# Connectors.net
KiCad netlist of a schematic drawn in Altium Designer
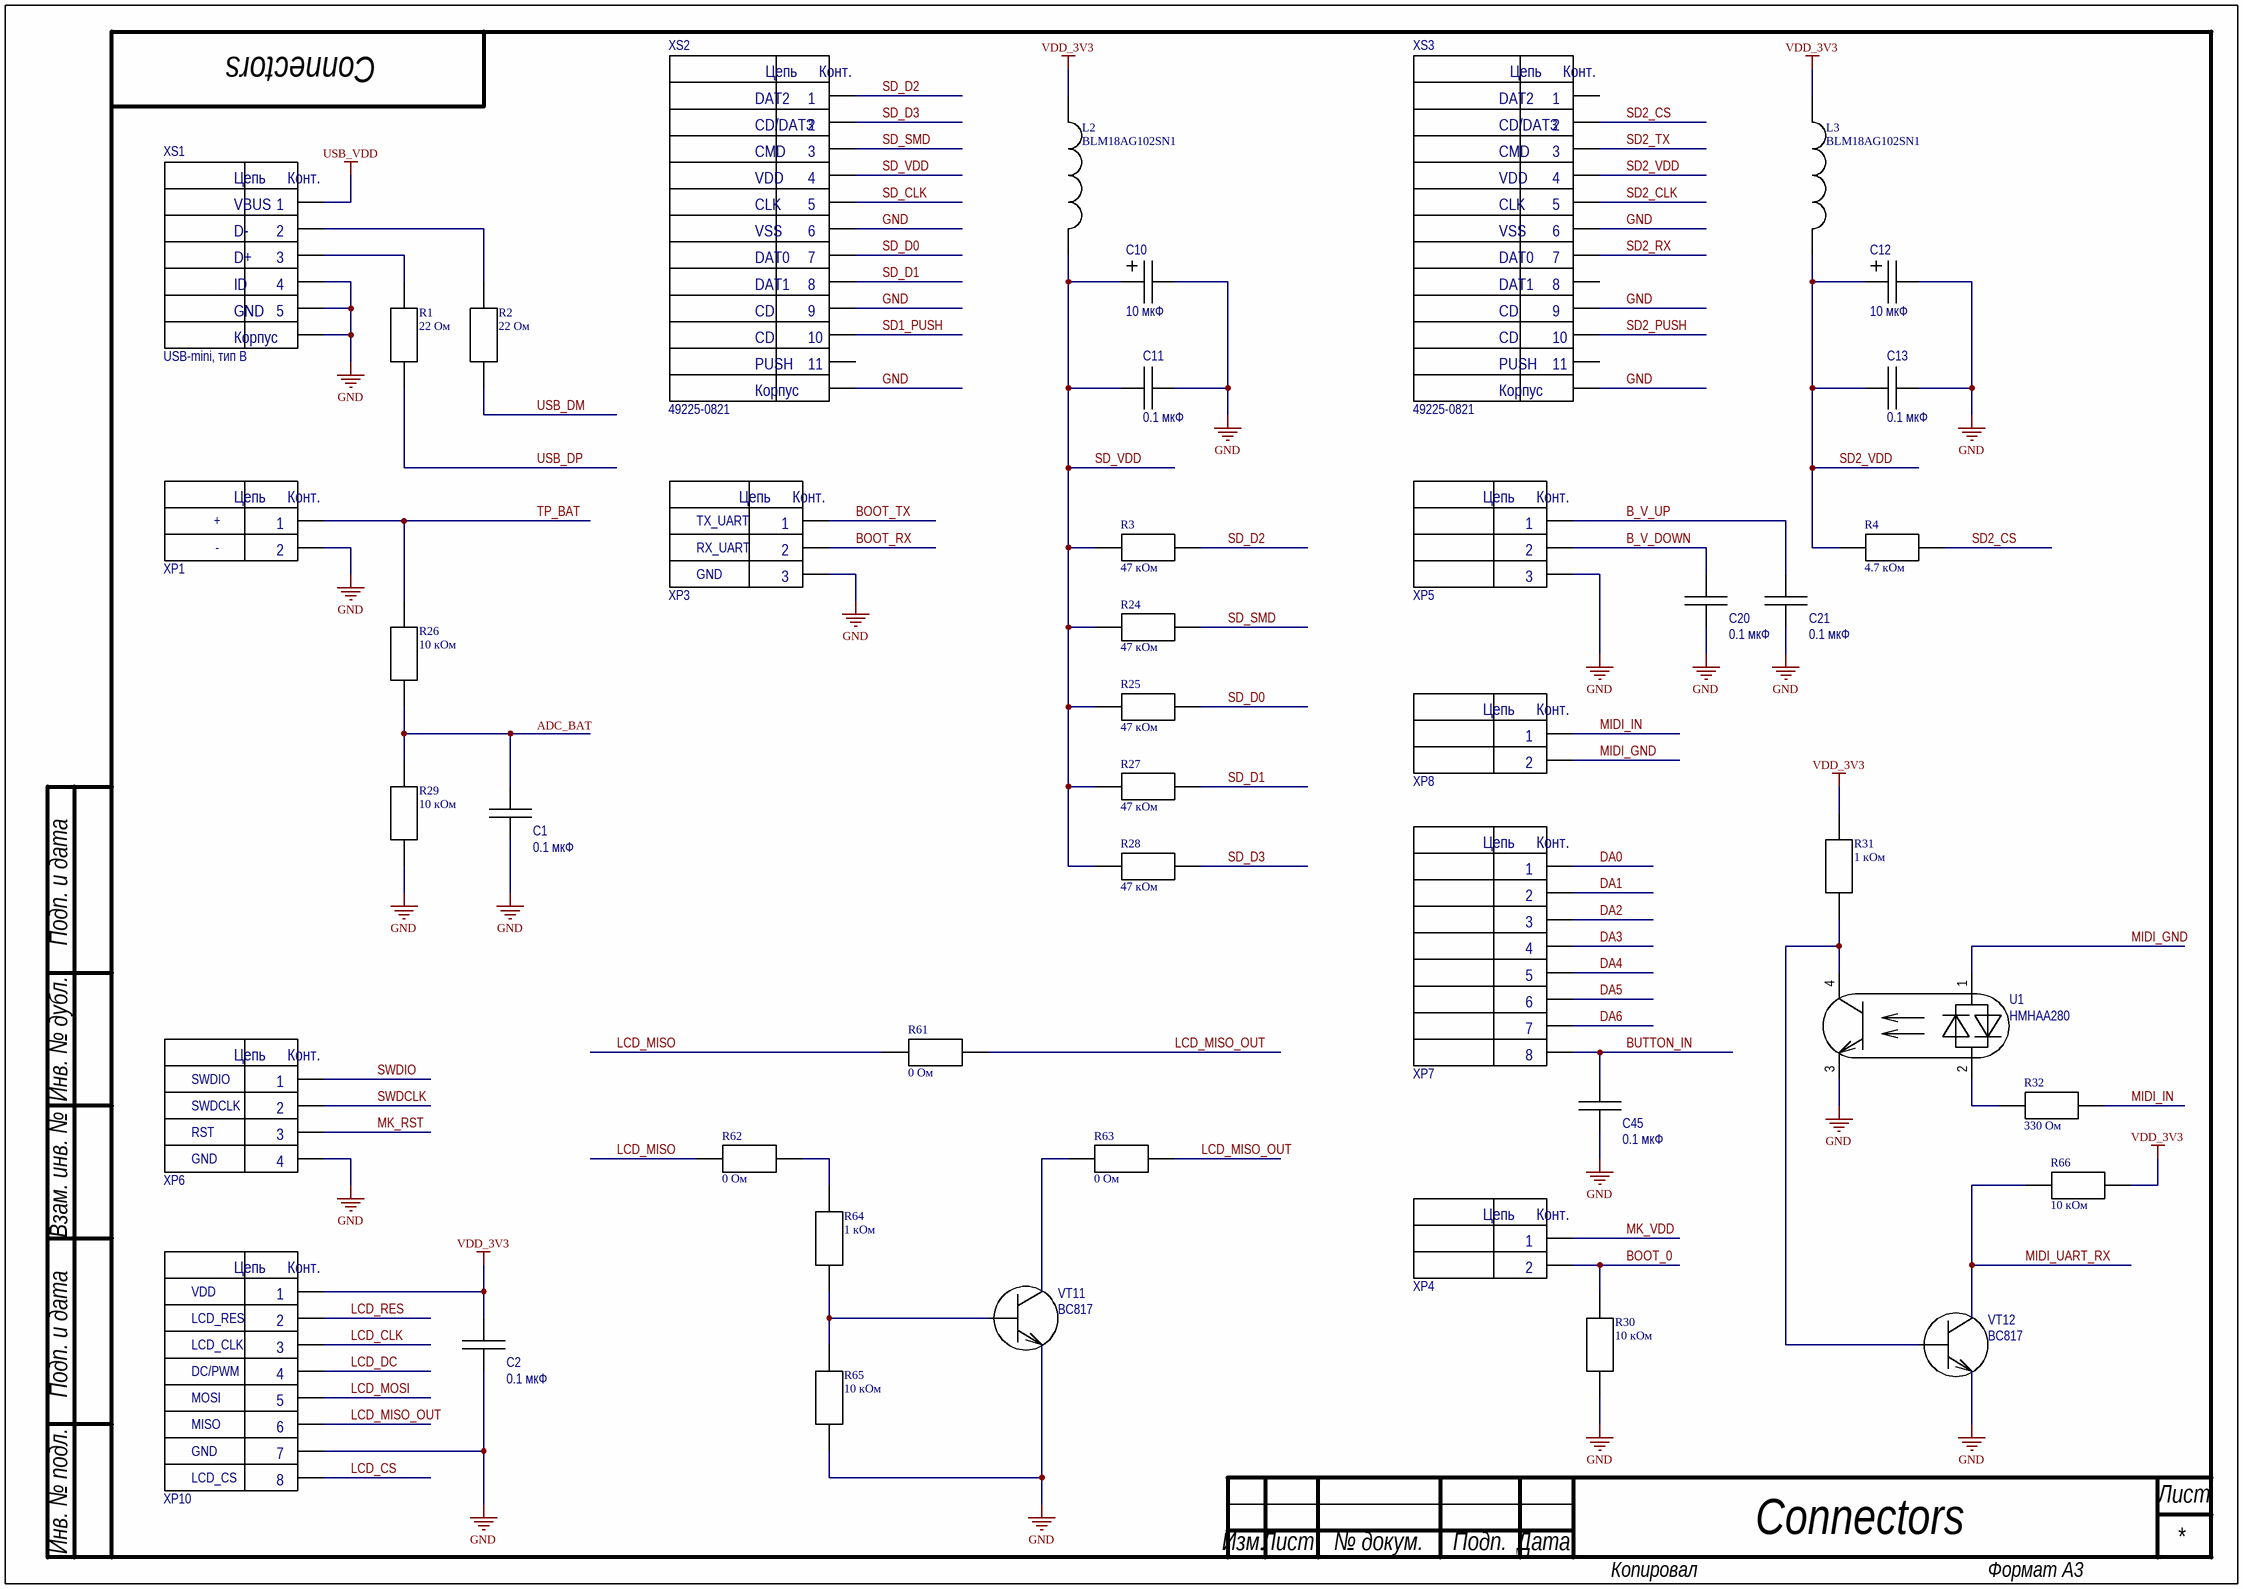
[diagram p0: Connectors.SchDoc]

(export (version "E")
  (design (tool "Eeschema 10.0.6"))
  (components
    (comp (ref "C1")
      (value "0.1 мкФ")
      (footprint "C 1206")
      (description "SMD Capacitor 1206")
      (fields
        (field (name "TOLERANCE") "/Укажите допуск в процентах/")
        (field (name "MANUFACTURER") "/Укажите компанию-производителя/")
      )
      (libsource (lib "my_lib") (part "CAP 1206"))
    )
    (comp (ref "C2")
      (value "0.1 мкФ")
      (footprint "C 1206")
      (description "SMD Capacitor 1206")
      (fields
        (field (name "TOLERANCE") "/Укажите допуск в процентах/")
        (field (name "MANUFACTURER") "/Укажите компанию-производителя/")
      )
      (libsource (lib "my_lib") (part "CAP 1206"))
    )
    (comp (ref "C10")
      (value "10 мкФ")
      (footprint "C TAN_C")
      (description "SMD Tantalium Capacitor C")
      (fields
        (field (name "TOLERANCE") "/Укажите допуск в процентах/")
        (field (name "MANUFACTURER") "/Укажите компанию-производителя/")
      )
      (libsource (lib "my_lib") (part "CAP TAN_C"))
    )
    (comp (ref "C11")
      (value "0.1 мкФ")
      (footprint "C 1206")
      (description "SMD Capacitor 1206")
      (fields
        (field (name "TOLERANCE") "/Укажите допуск в процентах/")
        (field (name "MANUFACTURER") "/Укажите компанию-производителя/")
      )
      (libsource (lib "my_lib") (part "CAP 1206"))
    )
    (comp (ref "C12")
      (value "10 мкФ")
      (footprint "C TAN_C")
      (description "SMD Tantalium Capacitor C")
      (fields
        (field (name "TOLERANCE") "/Укажите допуск в процентах/")
        (field (name "MANUFACTURER") "/Укажите компанию-производителя/")
      )
      (libsource (lib "my_lib") (part "CAP TAN_C"))
    )
    (comp (ref "C13")
      (value "0.1 мкФ")
      (footprint "C 1206")
      (description "SMD Capacitor 1206")
      (fields
        (field (name "TOLERANCE") "/Укажите допуск в процентах/")
        (field (name "MANUFACTURER") "/Укажите компанию-производителя/")
      )
      (libsource (lib "my_lib") (part "CAP 1206"))
    )
    (comp (ref "C20")
      (value "0.1 мкФ")
      (footprint "C 1206")
      (description "SMD Capacitor 1206")
      (fields
        (field (name "TOLERANCE") "/Укажите допуск в процентах/")
        (field (name "MANUFACTURER") "/Укажите компанию-производителя/")
      )
      (libsource (lib "my_lib") (part "CAP 1206"))
    )
    (comp (ref "C21")
      (value "0.1 мкФ")
      (footprint "C 1206")
      (description "SMD Capacitor 1206")
      (fields
        (field (name "TOLERANCE") "/Укажите допуск в процентах/")
        (field (name "MANUFACTURER") "/Укажите компанию-производителя/")
      )
      (libsource (lib "my_lib") (part "CAP 1206"))
    )
    (comp (ref "C45")
      (value "0.1 мкФ")
      (footprint "C 1206")
      (description "SMD Capacitor 1206")
      (fields
        (field (name "TOLERANCE") "/Укажите допуск в процентах/")
        (field (name "MANUFACTURER") "/Укажите компанию-производителя/")
      )
      (libsource (lib "my_lib") (part "CAP 1206"))
    )
    (comp (ref "L2")
      (value "BLM18AG102SN1")
      (footprint "FB 0603")
      (libsource (lib "my_lib") (part "BLM18AG102SN1"))
    )
    (comp (ref "L3")
      (value "BLM18AG102SN1")
      (footprint "FB 0603")
      (libsource (lib "my_lib") (part "BLM18AG102SN1"))
    )
    (comp (ref "R1") (value "22 Ом") (footprint "RES 0805") (libsource (lib "my_lib") (part "RES 0805")))
    (comp (ref "R2") (value "22 Ом") (footprint "RES 0805") (libsource (lib "my_lib") (part "RES 0805")))
    (comp (ref "R3") (value "47 кОм") (footprint "RES 0805") (libsource (lib "my_lib") (part "RES 0805")))
    (comp (ref "R4") (value "4.7 кОм") (footprint "RES 0805") (libsource (lib "my_lib") (part "RES 0805")))
    (comp (ref "R24") (value "47 кОм") (footprint "RES 0805") (libsource (lib "my_lib") (part "RES 0805")))
    (comp (ref "R25") (value "47 кОм") (footprint "RES 0805") (libsource (lib "my_lib") (part "RES 0805")))
    (comp (ref "R26") (value "10 кОм") (footprint "RES 0805") (libsource (lib "my_lib") (part "RES 0805")))
    (comp (ref "R27") (value "47 кОм") (footprint "RES 0805") (libsource (lib "my_lib") (part "RES 0805")))
    (comp (ref "R28") (value "47 кОм") (footprint "RES 0805") (libsource (lib "my_lib") (part "RES 0805")))
    (comp (ref "R29") (value "10 кОм") (footprint "RES 0805") (libsource (lib "my_lib") (part "RES 0805")))
    (comp (ref "R30") (value "10 кОм") (footprint "RES 0805") (libsource (lib "my_lib") (part "RES 0805")))
    (comp (ref "R31") (value "1 кОм") (footprint "RES 0805") (libsource (lib "my_lib") (part "RES 0805")))
    (comp (ref "R32") (value "330 Ом") (footprint "RES 0805") (libsource (lib "my_lib") (part "RES 0805")))
    (comp (ref "R61") (value "0 Ом") (footprint "RES 0805") (libsource (lib "my_lib") (part "RES 0805")))
    (comp (ref "R62") (value "0 Ом") (footprint "RES 0805") (libsource (lib "my_lib") (part "RES 0805")))
    (comp (ref "R63") (value "0 Ом") (footprint "RES 0805") (libsource (lib "my_lib") (part "RES 0805")))
    (comp (ref "R64") (value "1 кОм") (footprint "RES 0805") (libsource (lib "my_lib") (part "RES 0805")))
    (comp (ref "R65") (value "10 кОм") (footprint "RES 0805") (libsource (lib "my_lib") (part "RES 0805")))
    (comp (ref "R66") (value "10 кОм") (footprint "RES 0805") (libsource (lib "my_lib") (part "RES 0805")))
    (comp (ref "U1")
      (value "HMHAA280")
      (footprint "MFP-4L")
      (description "AC Input Half Pitch Mini-Flat Package 4-pin Optocoupler")
      (fields (field (name "MANUFACTURER") "Fairchild Semiconductor"))
      (libsource (lib "my_lib") (part "HMHAA280"))
    )
    (comp (ref "VT11")
      (value "BC817")
      (footprint "SOT-23")
      (description "NPN general-purpose transistor")
      (fields (field (name "MANUFACTURER") "NXP"))
      (libsource (lib "my_lib") (part "BC817"))
    )
    (comp (ref "VT12")
      (value "BC817")
      (footprint "SOT-23")
      (description "NPN general-purpose transistor")
      (fields (field (name "MANUFACTURER") "NXP"))
      (libsource (lib "my_lib") (part "BC817"))
    )
    (comp (ref "XP1")
      (value "PLS-2")
      (footprint "PLS-2")
      (description "PLS connector")
      (fields (field (name "MANUFACTURER") "NONAME"))
      (libsource (lib "my_lib") (part "PLS-2"))
    )
    (comp (ref "XP3")
      (value "PLS-3")
      (footprint "PLS-3")
      (description "PLS connector")
      (fields (field (name "MANUFACTURER") "NONAME"))
      (libsource (lib "my_lib") (part "PLS-3"))
    )
    (comp (ref "XP4")
      (value "PLS-2")
      (footprint "PLS-2")
      (description "PLS connector")
      (fields (field (name "MANUFACTURER") "NONAME"))
      (libsource (lib "my_lib") (part "PLS-2"))
    )
    (comp (ref "XP5")
      (value "PLS-3")
      (footprint "PLS-3")
      (description "PLS connector")
      (fields (field (name "MANUFACTURER") "NONAME"))
      (libsource (lib "my_lib") (part "PLS-3"))
    )
    (comp (ref "XP6")
      (value "PLD-4")
      (footprint "PLD-4")
      (description "PLD connector")
      (fields (field (name "MANUFACTURER") "NONAME"))
      (libsource (lib "my_lib") (part "PLD-4"))
    )
    (comp (ref "XP7")
      (value "PLD-8")
      (footprint "PLD-8")
      (description "PLD connector")
      (fields (field (name "MANUFACTURER") "NONAME"))
      (libsource (lib "my_lib") (part "PLD-8"))
    )
    (comp (ref "XP8")
      (value "PLS-2")
      (footprint "PLS-2")
      (description "PLS connector")
      (fields (field (name "MANUFACTURER") "NONAME"))
      (libsource (lib "my_lib") (part "PLS-2"))
    )
    (comp (ref "XP10")
      (value "PLD-8")
      (footprint "PLD-8")
      (description "PLD connector")
      (fields (field (name "MANUFACTURER") "NONAME"))
      (libsource (lib "my_lib") (part "PLD-8"))
    )
    (comp (ref "XS1")
      (value "USB-mini, тип B")
      (footprint "USB_mini_B")
      (description "USB-mini-B connector")
      (fields (field (name "MANUFACTURER") "NONAME"))
      (libsource (lib "my_lib") (part "USB-mini_B"))
    )
    (comp (ref "XS2")
      (value "49225-0821")
      (footprint "MOLEX 49225-0821")
      (description "MOLEX MicroSD connector")
      (fields (field (name "MANUFACTURER") "Molex"))
      (libsource (lib "my_lib") (part "49225-0821"))
    )
    (comp (ref "XS3")
      (value "49225-0821")
      (footprint "MOLEX 49225-0821")
      (description "MOLEX MicroSD connector")
      (fields (field (name "MANUFACTURER") "Molex"))
      (libsource (lib "my_lib") (part "49225-0821"))
    )
  )
  (nets
    (net (code "1") (name "/ADC_BAT") (class "Default")
      (node (ref "C1") (pin "1") (pinfunction "1_1") (pintype "passive"))
      (node (ref "R26") (pin "1") (pinfunction "1_1") (pintype "passive"))
      (node (ref "R29") (pin "2") (pinfunction "2_2") (pintype "passive"))
    )
    (net (code "2") (name "/BOOT_0") (class "Default")
      (node (ref "R30") (pin "2") (pinfunction "2_2") (pintype "passive"))
      (node (ref "XP4") (pin "2") (pinfunction "2_2") (pintype "passive"))
    )
    (net (code "3") (name "/BOOT_RX") (class "Default")
      (node (ref "XP3") (pin "2") (pinfunction "2_2") (pintype "passive"))
    )
    (net (code "4") (name "/BOOT_TX") (class "Default")
      (node (ref "XP3") (pin "1") (pinfunction "1_1") (pintype "passive"))
    )
    (net (code "5") (name "/BUTTON_IN") (class "Default")
      (node (ref "C45") (pin "1") (pinfunction "1_1") (pintype "passive"))
      (node (ref "XP7") (pin "8") (pinfunction "8_8") (pintype "passive"))
    )
    (net (code "6") (name "/B_V_DOWN") (class "Default")
      (node (ref "C20") (pin "1") (pinfunction "1_1") (pintype "passive"))
      (node (ref "XP5") (pin "2") (pinfunction "2_2") (pintype "passive"))
    )
    (net (code "7") (name "/B_V_UP") (class "Default")
      (node (ref "C21") (pin "1") (pinfunction "1_1") (pintype "passive"))
      (node (ref "XP5") (pin "1") (pinfunction "1_1") (pintype "passive"))
    )
    (net (code "8") (name "/DA0") (class "Default")
      (node (ref "XP7") (pin "1") (pinfunction "1_1") (pintype "passive"))
    )
    (net (code "9") (name "/DA1") (class "Default")
      (node (ref "XP7") (pin "2") (pinfunction "2_2") (pintype "passive"))
    )
    (net (code "10") (name "/DA2") (class "Default")
      (node (ref "XP7") (pin "3") (pinfunction "3_3") (pintype "passive"))
    )
    (net (code "11") (name "/DA3") (class "Default")
      (node (ref "XP7") (pin "4") (pinfunction "4_4") (pintype "passive"))
    )
    (net (code "12") (name "/DA4") (class "Default")
      (node (ref "XP7") (pin "5") (pinfunction "5_5") (pintype "passive"))
    )
    (net (code "13") (name "/DA5") (class "Default")
      (node (ref "XP7") (pin "6") (pinfunction "6_6") (pintype "passive"))
    )
    (net (code "14") (name "/DA6") (class "Default")
      (node (ref "XP7") (pin "7") (pinfunction "7_7") (pintype "passive"))
    )
    (net (code "15") (name "/LCD_CLK") (class "Default")
      (node (ref "XP10") (pin "3") (pinfunction "3_3") (pintype "passive"))
    )
    (net (code "16") (name "/LCD_CS") (class "Default")
      (node (ref "XP10") (pin "8") (pinfunction "8_8") (pintype "passive"))
    )
    (net (code "17") (name "/LCD_DC") (class "Default")
      (node (ref "XP10") (pin "4") (pinfunction "4_4") (pintype "passive"))
    )
    (net (code "18") (name "/LCD_MISO") (class "Default")
      (node (ref "R61") (pin "1") (pinfunction "1_1") (pintype "passive"))
      (node (ref "R62") (pin "2") (pinfunction "2_2") (pintype "passive"))
    )
    (net (code "19") (name "/LCD_MISO_OUT") (class "Default")
      (node (ref "R61") (pin "2") (pinfunction "2_2") (pintype "passive"))
      (node (ref "R63") (pin "1") (pinfunction "1_1") (pintype "passive"))
      (node (ref "XP10") (pin "6") (pinfunction "6_6") (pintype "passive"))
    )
    (net (code "20") (name "/LCD_MOSI") (class "Default")
      (node (ref "XP10") (pin "5") (pinfunction "5_5") (pintype "passive"))
    )
    (net (code "21") (name "/LCD_RES") (class "Default")
      (node (ref "XP10") (pin "2") (pinfunction "2_2") (pintype "passive"))
    )
    (net (code "22") (name "/MIDI_GND") (class "Default")
      (node (ref "U1") (pin "1") (pinfunction "AC_1") (pintype "passive"))
      (node (ref "XP8") (pin "2") (pinfunction "2_2") (pintype "passive"))
    )
    (net (code "23") (name "/MIDI_IN") (class "Default")
      (node (ref "R32") (pin "2") (pinfunction "2_2") (pintype "passive"))
      (node (ref "XP8") (pin "1") (pinfunction "1_1") (pintype "passive"))
    )
    (net (code "24") (name "/MIDI_UART_RX") (class "Default")
      (node (ref "R66") (pin "1") (pinfunction "1_1") (pintype "passive"))
      (node (ref "VT12") (pin "3") (pinfunction "C_3") (pintype "passive"))
    )
    (net (code "25") (name "/MK_RST") (class "Default")
      (node (ref "XP6") (pin "3") (pinfunction "3_3") (pintype "passive"))
    )
    (net (code "26") (name "/MK_VDD") (class "Default")
      (node (ref "XP4") (pin "1") (pinfunction "1_1") (pintype "passive"))
    )
    (net (code "27") (name "/SD1_PUSH") (class "Default")
      (node (ref "XS2") (pin "10") (pinfunction "10_10") (pintype "passive"))
    )
    (net (code "28") (name "/SD2_CLK") (class "Default")
      (node (ref "XS3") (pin "5") (pinfunction "5_5") (pintype "passive"))
    )
    (net (code "29") (name "/SD2_CS") (class "Default")
      (node (ref "R4") (pin "2") (pinfunction "2_2") (pintype "passive"))
      (node (ref "XS3") (pin "2") (pinfunction "2_2") (pintype "passive"))
    )
    (net (code "30") (name "/SD2_PUSH") (class "Default")
      (node (ref "XS3") (pin "10") (pinfunction "10_10") (pintype "passive"))
    )
    (net (code "31") (name "/SD2_RX") (class "Default")
      (node (ref "XS3") (pin "7") (pinfunction "7_7") (pintype "passive"))
    )
    (net (code "32") (name "/SD2_TX") (class "Default")
      (node (ref "XS3") (pin "3") (pinfunction "3_3") (pintype "passive"))
    )
    (net (code "33") (name "/SD2_VDD") (class "Default")
      (node (ref "C12") (pin "1") (pinfunction "1_1") (pintype "passive"))
      (node (ref "C13") (pin "1") (pinfunction "1_1") (pintype "passive"))
      (node (ref "L3") (pin "2") (pinfunction "2_2") (pintype "passive"))
      (node (ref "R4") (pin "1") (pinfunction "1_1") (pintype "passive"))
      (node (ref "XS3") (pin "4") (pinfunction "4_4") (pintype "passive"))
    )
    (net (code "34") (name "/SD_CLK") (class "Default")
      (node (ref "XS2") (pin "5") (pinfunction "5_5") (pintype "passive"))
    )
    (net (code "35") (name "/SD_D0") (class "Default")
      (node (ref "R25") (pin "2") (pinfunction "2_2") (pintype "passive"))
      (node (ref "XS2") (pin "7") (pinfunction "7_7") (pintype "passive"))
    )
    (net (code "36") (name "/SD_D1") (class "Default")
      (node (ref "R27") (pin "2") (pinfunction "2_2") (pintype "passive"))
      (node (ref "XS2") (pin "8") (pinfunction "8_8") (pintype "passive"))
    )
    (net (code "37") (name "/SD_D2") (class "Default")
      (node (ref "R3") (pin "2") (pinfunction "2_2") (pintype "passive"))
      (node (ref "XS2") (pin "1") (pinfunction "1_1") (pintype "passive"))
    )
    (net (code "38") (name "/SD_D3") (class "Default")
      (node (ref "R28") (pin "2") (pinfunction "2_2") (pintype "passive"))
      (node (ref "XS2") (pin "2") (pinfunction "2_2") (pintype "passive"))
    )
    (net (code "39") (name "/SD_SMD") (class "Default")
      (node (ref "R24") (pin "2") (pinfunction "2_2") (pintype "passive"))
      (node (ref "XS2") (pin "3") (pinfunction "3_3") (pintype "passive"))
    )
    (net (code "40") (name "/SD_VDD") (class "Default")
      (node (ref "C10") (pin "1") (pinfunction "1_1") (pintype "passive"))
      (node (ref "C11") (pin "1") (pinfunction "1_1") (pintype "passive"))
      (node (ref "L2") (pin "2") (pinfunction "2_2") (pintype "passive"))
      (node (ref "R24") (pin "1") (pinfunction "1_1") (pintype "passive"))
      (node (ref "R25") (pin "1") (pinfunction "1_1") (pintype "passive"))
      (node (ref "R27") (pin "1") (pinfunction "1_1") (pintype "passive"))
      (node (ref "R28") (pin "1") (pinfunction "1_1") (pintype "passive"))
      (node (ref "R3") (pin "1") (pinfunction "1_1") (pintype "passive"))
      (node (ref "XS2") (pin "4") (pinfunction "4_4") (pintype "passive"))
    )
    (net (code "41") (name "/SWDCLK") (class "Default")
      (node (ref "XP6") (pin "2") (pinfunction "2_2") (pintype "passive"))
    )
    (net (code "42") (name "/SWDIO") (class "Default")
      (node (ref "XP6") (pin "1") (pinfunction "1_1") (pintype "passive"))
    )
    (net (code "43") (name "/TP_BAT") (class "Default")
      (node (ref "R26") (pin "2") (pinfunction "2_2") (pintype "passive"))
      (node (ref "XP1") (pin "1") (pinfunction "1_1") (pintype "passive"))
    )
    (net (code "44") (name "/USB_DM") (class "Default")
      (node (ref "R2") (pin "1") (pinfunction "1_1") (pintype "passive"))
    )
    (net (code "45") (name "/USB_DP") (class "Default")
      (node (ref "R1") (pin "1") (pinfunction "1_1") (pintype "passive"))
    )
    (net (code "46") (name "GND") (class "Default")
      (node (ref "C1") (pin "2") (pinfunction "2_2") (pintype "passive"))
      (node (ref "C10") (pin "2") (pinfunction "2_2") (pintype "passive"))
      (node (ref "C11") (pin "2") (pinfunction "2_2") (pintype "passive"))
      (node (ref "C12") (pin "2") (pinfunction "2_2") (pintype "passive"))
      (node (ref "C13") (pin "2") (pinfunction "2_2") (pintype "passive"))
      (node (ref "C2") (pin "2") (pinfunction "2_2") (pintype "passive"))
      (node (ref "C20") (pin "2") (pinfunction "2_2") (pintype "passive"))
      (node (ref "C21") (pin "2") (pinfunction "2_2") (pintype "passive"))
      (node (ref "C45") (pin "2") (pinfunction "2_2") (pintype "passive"))
      (node (ref "R29") (pin "1") (pinfunction "1_1") (pintype "passive"))
      (node (ref "R30") (pin "1") (pinfunction "1_1") (pintype "passive"))
      (node (ref "R65") (pin "1") (pinfunction "1_1") (pintype "passive"))
      (node (ref "U1") (pin "3") (pinfunction "E_3") (pintype "passive"))
      (node (ref "VT11") (pin "2") (pinfunction "E_2") (pintype "passive"))
      (node (ref "VT12") (pin "2") (pinfunction "E_2") (pintype "passive"))
      (node (ref "XP1") (pin "2") (pinfunction "2_2") (pintype "passive"))
      (node (ref "XP10") (pin "7") (pinfunction "7_7") (pintype "passive"))
      (node (ref "XP3") (pin "3") (pinfunction "3_3") (pintype "passive"))
      (node (ref "XP5") (pin "3") (pinfunction "3_3") (pintype "passive"))
      (node (ref "XP6") (pin "4") (pinfunction "4_4") (pintype "passive"))
      (node (ref "XS1") (pin "0") (pinfunction "0_0") (pintype "passive"))
      (node (ref "XS1") (pin "4") (pinfunction "CASE_4") (pintype "passive"))
      (node (ref "XS1") (pin "5") (pinfunction "GND_5") (pintype "passive"))
      (node (ref "XS2") (pin "0") (pinfunction "0_0") (pintype "passive"))
      (node (ref "XS2") (pin "6") (pinfunction "6_6") (pintype "passive"))
      (node (ref "XS2") (pin "9") (pinfunction "9_9") (pintype "passive"))
      (node (ref "XS3") (pin "0") (pinfunction "0_0") (pintype "passive"))
      (node (ref "XS3") (pin "6") (pinfunction "6_6") (pintype "passive"))
      (node (ref "XS3") (pin "9") (pinfunction "9_9") (pintype "passive"))
    )
    (net (code "47") (name "Net-(R62-Pad1)") (class "Default")
      (node (ref "R62") (pin "1") (pinfunction "1_1") (pintype "passive"))
      (node (ref "R64") (pin "2") (pinfunction "2_2") (pintype "passive"))
    )
    (net (code "48") (name "Net-(U1-C)") (class "Default")
      (node (ref "R31") (pin "1") (pinfunction "1_1") (pintype "passive"))
      (node (ref "U1") (pin "4") (pinfunction "C_4") (pintype "passive"))
      (node (ref "VT12") (pin "1") (pinfunction "B_1") (pintype "passive"))
    )
    (net (code "49") (name "Net-(U1-CA)") (class "Default")
      (node (ref "R32") (pin "1") (pinfunction "1_1") (pintype "passive"))
      (node (ref "U1") (pin "2") (pinfunction "CA_2") (pintype "passive"))
    )
    (net (code "50") (name "Net-(VT11-B)") (class "Default")
      (node (ref "R64") (pin "1") (pinfunction "1_1") (pintype "passive"))
      (node (ref "R65") (pin "2") (pinfunction "2_2") (pintype "passive"))
      (node (ref "VT11") (pin "1") (pinfunction "B_1") (pintype "passive"))
    )
    (net (code "51") (name "Net-(VT11-C)") (class "Default")
      (node (ref "R63") (pin "2") (pinfunction "2_2") (pintype "passive"))
      (node (ref "VT11") (pin "3") (pinfunction "C_3") (pintype "passive"))
    )
    (net (code "52") (name "Net-(XS1-D+)") (class "Default")
      (node (ref "R1") (pin "2") (pinfunction "2_2") (pintype "passive"))
      (node (ref "XS1") (pin "3") (pinfunction "D+_3") (pintype "passive"))
    )
    (net (code "53") (name "Net-(XS1-D-)") (class "Default")
      (node (ref "R2") (pin "2") (pinfunction "2_2") (pintype "passive"))
      (node (ref "XS1") (pin "2") (pinfunction "D-_2") (pintype "passive"))
    )
    (net (code "54") (name "USB_VDD") (class "Default")
      (node (ref "XS1") (pin "1") (pinfunction "VBUS_1") (pintype "passive"))
    )
    (net (code "55") (name "VDD_3V3") (class "Default")
      (node (ref "C2") (pin "1") (pinfunction "1_1") (pintype "passive"))
      (node (ref "L2") (pin "1") (pinfunction "1_1") (pintype "passive"))
      (node (ref "L3") (pin "1") (pinfunction "1_1") (pintype "passive"))
      (node (ref "R31") (pin "2") (pinfunction "2_2") (pintype "passive"))
      (node (ref "R66") (pin "2") (pinfunction "2_2") (pintype "passive"))
      (node (ref "XP10") (pin "1") (pinfunction "1_1") (pintype "passive"))
    )
    (net (code "56") (name "unconnected-(XS2-Pad11)") (class "Default")
      (node (ref "XS2") (pin "11") (pinfunction "11_11") (pintype "passive"))
    )
    (net (code "57") (name "unconnected-(XS3-Pad1)") (class "Default")
      (node (ref "XS3") (pin "1") (pinfunction "1_1") (pintype "passive"))
    )
    (net (code "58") (name "unconnected-(XS3-Pad8)") (class "Default")
      (node (ref "XS3") (pin "8") (pinfunction "8_8") (pintype "passive"))
    )
    (net (code "59") (name "unconnected-(XS3-Pad11)") (class "Default")
      (node (ref "XS3") (pin "11") (pinfunction "11_11") (pintype "passive"))
    )
  )
)
